# LEDBlink.net
KiCad netlist of a schematic drawn in EAGLE
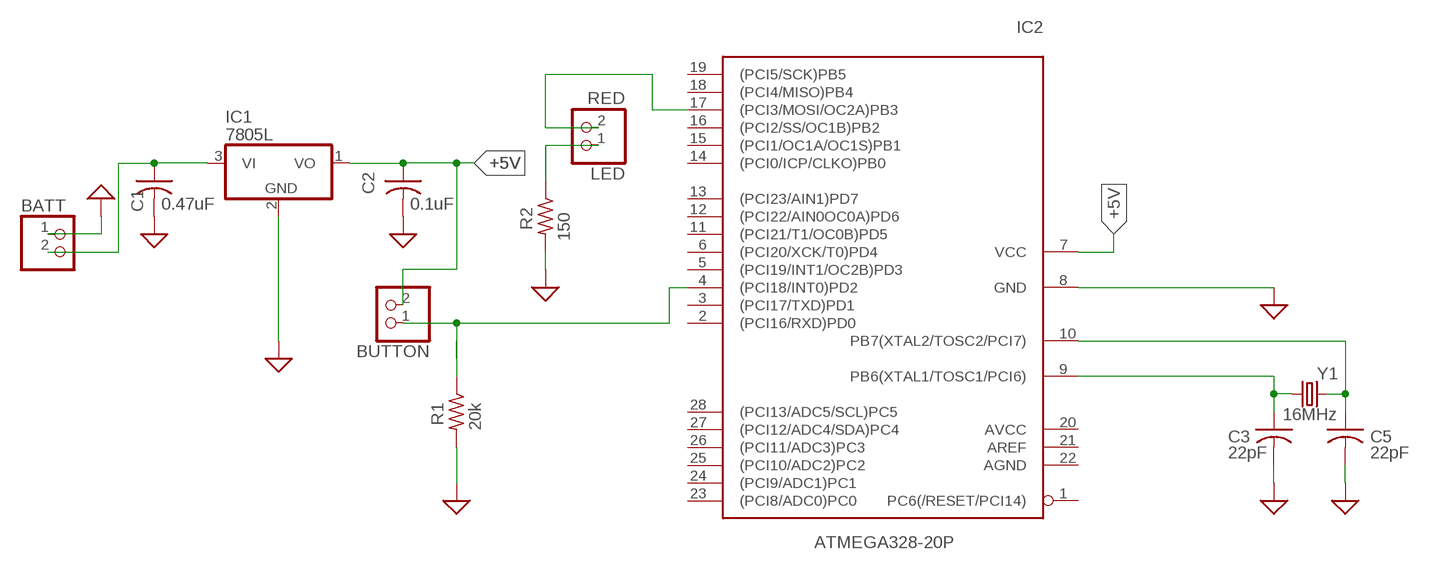
[diagram p0: schematic, sheet 1]

(export (version "E")
  (design (tool "Eeschema 10.0.6"))
  (components
    (comp (ref "BATT")
      (value "PINHD-1X2/90")
      (footprint "eagle-import:1X02_90")
      (libsource (lib "eagle-import") (part "PINHD-1X2/90"))
    )
    (comp (ref "BUTTON")
      (value "PINHD-1X2/90")
      (footprint "eagle-import:1X02_90")
      (libsource (lib "eagle-import") (part "PINHD-1X2/90"))
    )
    (comp (ref "C1")
      (value "0.47uF")
      (footprint "eagle-import:C0805")
      (libsource (lib "eagle-import") (part "C-USC0805"))
    )
    (comp (ref "C2")
      (value "0.1uF")
      (footprint "eagle-import:C0805")
      (libsource (lib "eagle-import") (part "C-USC0805"))
    )
    (comp (ref "C3")
      (value "22pF")
      (footprint "eagle-import:C0805")
      (libsource (lib "eagle-import") (part "C-USC0805"))
    )
    (comp (ref "C5")
      (value "22pF")
      (footprint "eagle-import:C0805")
      (libsource (lib "eagle-import") (part "C-USC0805"))
    )
    (comp (ref "IC1")
      (value "7805L")
      (footprint "eagle-import:TO92")
      (libsource (lib "eagle-import") (part "78L05"))
    )
    (comp (ref "IC2")
      (value "ATMEGA328-20P")
      (footprint "eagle-import:DIL28-3")
      (libsource (lib "eagle-import") (part "ATMEGA328P-20"))
    )
    (comp (ref "LED")
      (value "RED")
      (footprint "eagle-import:1X02_90")
      (libsource (lib "eagle-import") (part "PINHD-1X2/90"))
    )
    (comp (ref "R1")
      (value "20k")
      (footprint "eagle-import:R0805")
      (libsource (lib "eagle-import") (part "R-US_R0805"))
    )
    (comp (ref "R2")
      (value "150")
      (footprint "eagle-import:R0805")
      (libsource (lib "eagle-import") (part "R-US_R0805"))
    )
    (comp (ref "Y1")
      (value "16MHz")
      (footprint "eagle-import:HC49US")
      (libsource (lib "eagle-import") (part "CRYSTAL-16MHZPTH-HC49US"))
    )
  )
  (nets
    (net (code "1") (name "+5V") (class "Default")
      (node (ref "BUTTON") (pin "2") (pinfunction "2_2") (pintype "passive"))
      (node (ref "C2") (pin "1") (pinfunction "1_1") (pintype "passive"))
      (node (ref "IC1") (pin "1") (pinfunction "VO_1") (pintype "passive"))
      (node (ref "IC2") (pin "7") (pinfunction "VCC_7") (pintype "bidirectional"))
    )
    (net (code "2") (name "Net-(IC1-VI)") (class "Default")
      (node (ref "BATT") (pin "2") (pinfunction "2_2") (pintype "passive"))
      (node (ref "C1") (pin "1") (pinfunction "1_1") (pintype "passive"))
      (node (ref "IC1") (pin "3") (pinfunction "VI_3") (pintype "input"))
    )
    (net (code "3") (name "Net-(IC2-(PCI3{slash}MOSI{slash}OC2A)PB3)") (class "Default")
      (node (ref "IC2") (pin "17") (pinfunction "(PCI3/MOSI/OC2A)PB3_17") (pintype "bidirectional"))
      (node (ref "LED") (pin "2") (pinfunction "2_2") (pintype "passive"))
    )
    (net (code "4") (name "Net-(IC2-(PCI18{slash}INT0)PD2)") (class "Default")
      (node (ref "BUTTON") (pin "1") (pinfunction "1_1") (pintype "passive"))
      (node (ref "IC2") (pin "4") (pinfunction "(PCI18/INT0)PD2_4") (pintype "bidirectional"))
      (node (ref "R1") (pin "1") (pinfunction "1_1") (pintype "passive"))
    )
    (net (code "5") (name "Net-(IC2-PB6(XTAL1{slash}TOSC1{slash}PCI6))") (class "Default")
      (node (ref "C3") (pin "1") (pinfunction "1_1") (pintype "passive"))
      (node (ref "IC2") (pin "9") (pinfunction "PB6(XTAL1/TOSC1/PCI6)_9") (pintype "bidirectional"))
      (node (ref "Y1") (pin "1") (pinfunction "1_1") (pintype "passive"))
    )
    (net (code "6") (name "Net-(IC2-PB7(XTAL2{slash}TOSC2{slash}PCI7))") (class "Default")
      (node (ref "C5") (pin "1") (pinfunction "1_1") (pintype "passive"))
      (node (ref "IC2") (pin "10") (pinfunction "PB7(XTAL2/TOSC2/PCI7)_10") (pintype "bidirectional"))
      (node (ref "Y1") (pin "2") (pinfunction "2_2") (pintype "passive"))
    )
    (net (code "7") (name "Net-(LED-Pad1)") (class "Default")
      (node (ref "LED") (pin "1") (pinfunction "1_1") (pintype "passive"))
      (node (ref "R2") (pin "1") (pinfunction "1_1") (pintype "passive"))
    )
    (net (code "8") (name "SUP") (class "Default")
      (node (ref "BATT") (pin "1") (pinfunction "1_1") (pintype "passive"))
      (node (ref "C1") (pin "2") (pinfunction "2_2") (pintype "passive"))
      (node (ref "C2") (pin "2") (pinfunction "2_2") (pintype "passive"))
      (node (ref "C3") (pin "2") (pinfunction "2_2") (pintype "passive"))
      (node (ref "C5") (pin "2") (pinfunction "2_2") (pintype "passive"))
      (node (ref "IC1") (pin "2") (pinfunction "GND_2") (pintype "passive"))
      (node (ref "IC2") (pin "8") (pinfunction "GND_8") (pintype "bidirectional"))
      (node (ref "R1") (pin "2") (pinfunction "2_2") (pintype "passive"))
      (node (ref "R2") (pin "2") (pinfunction "2_2") (pintype "passive"))
    )
    (net (code "9") (name "unconnected-(IC2-(PCI0{slash}ICP{slash}CLKO)PB0-Pad14)") (class "Default")
      (node (ref "IC2") (pin "14") (pinfunction "(PCI0/ICP/CLKO)PB0_14") (pintype "bidirectional"))
    )
    (net (code "10") (name "unconnected-(IC2-(PCI1{slash}OC1A{slash}OC1S)PB1-Pad15)") (class "Default")
      (node (ref "IC2") (pin "15") (pinfunction "(PCI1/OC1A/OC1S)PB1_15") (pintype "bidirectional"))
    )
    (net (code "11") (name "unconnected-(IC2-(PCI2{slash}SS{slash}OC1B)PB2-Pad16)") (class "Default")
      (node (ref "IC2") (pin "16") (pinfunction "(PCI2/SS/OC1B)PB2_16") (pintype "bidirectional"))
    )
    (net (code "12") (name "unconnected-(IC2-(PCI4{slash}MISO)PB4-Pad18)") (class "Default")
      (node (ref "IC2") (pin "18") (pinfunction "(PCI4/MISO)PB4_18") (pintype "bidirectional"))
    )
    (net (code "13") (name "unconnected-(IC2-(PCI5{slash}SCK)PB5-Pad19)") (class "Default")
      (node (ref "IC2") (pin "19") (pinfunction "(PCI5/SCK)PB5_19") (pintype "bidirectional"))
    )
    (net (code "14") (name "unconnected-(IC2-(PCI8{slash}ADC0)PC0-Pad23)") (class "Default")
      (node (ref "IC2") (pin "23") (pinfunction "(PCI8/ADC0)PC0_23") (pintype "bidirectional"))
    )
    (net (code "15") (name "unconnected-(IC2-(PCI9{slash}ADC1)PC1-Pad24)") (class "Default")
      (node (ref "IC2") (pin "24") (pinfunction "(PCI9/ADC1)PC1_24") (pintype "bidirectional"))
    )
    (net (code "16") (name "unconnected-(IC2-(PCI10{slash}ADC2)PC2-Pad25)") (class "Default")
      (node (ref "IC2") (pin "25") (pinfunction "(PCI10/ADC2)PC2_25") (pintype "bidirectional"))
    )
    (net (code "17") (name "unconnected-(IC2-(PCI11{slash}ADC3)PC3-Pad26)") (class "Default")
      (node (ref "IC2") (pin "26") (pinfunction "(PCI11/ADC3)PC3_26") (pintype "bidirectional"))
    )
    (net (code "18") (name "unconnected-(IC2-(PCI12{slash}ADC4{slash}SDA)PC4-Pad27)") (class "Default")
      (node (ref "IC2") (pin "27") (pinfunction "(PCI12/ADC4/SDA)PC4_27") (pintype "bidirectional"))
    )
    (net (code "19") (name "unconnected-(IC2-(PCI13{slash}ADC5{slash}SCL)PC5-Pad28)") (class "Default")
      (node (ref "IC2") (pin "28") (pinfunction "(PCI13/ADC5/SCL)PC5_28") (pintype "bidirectional"))
    )
    (net (code "20") (name "unconnected-(IC2-(PCI16{slash}RXD)PD0-Pad2)") (class "Default")
      (node (ref "IC2") (pin "2") (pinfunction "(PCI16/RXD)PD0_2") (pintype "bidirectional"))
    )
    (net (code "21") (name "unconnected-(IC2-(PCI17{slash}TXD)PD1-Pad3)") (class "Default")
      (node (ref "IC2") (pin "3") (pinfunction "(PCI17/TXD)PD1_3") (pintype "bidirectional"))
    )
    (net (code "22") (name "unconnected-(IC2-(PCI19{slash}INT1{slash}OC2B)PD3-Pad5)") (class "Default")
      (node (ref "IC2") (pin "5") (pinfunction "(PCI19/INT1/OC2B)PD3_5") (pintype "bidirectional"))
    )
    (net (code "23") (name "unconnected-(IC2-(PCI20{slash}XCK{slash}T0)PD4-Pad6)") (class "Default")
      (node (ref "IC2") (pin "6") (pinfunction "(PCI20/XCK/T0)PD4_6") (pintype "bidirectional"))
    )
    (net (code "24") (name "unconnected-(IC2-(PCI21{slash}T1{slash}OC0B)PD5-Pad11)") (class "Default")
      (node (ref "IC2") (pin "11") (pinfunction "(PCI21/T1/OC0B)PD5_11") (pintype "bidirectional"))
    )
    (net (code "25") (name "unconnected-(IC2-(PCI22{slash}AIN0OC0A)PD6-Pad12)") (class "Default")
      (node (ref "IC2") (pin "12") (pinfunction "(PCI22/AIN0OC0A)PD6_12") (pintype "bidirectional"))
    )
    (net (code "26") (name "unconnected-(IC2-(PCI23{slash}AIN1)PD7-Pad13)") (class "Default")
      (node (ref "IC2") (pin "13") (pinfunction "(PCI23/AIN1)PD7_13") (pintype "bidirectional"))
    )
    (net (code "27") (name "unconnected-(IC2-AGND-Pad22)") (class "Default")
      (node (ref "IC2") (pin "22") (pinfunction "AGND_22") (pintype "bidirectional"))
    )
    (net (code "28") (name "unconnected-(IC2-AREF-Pad21)") (class "Default")
      (node (ref "IC2") (pin "21") (pinfunction "AREF_21") (pintype "bidirectional"))
    )
    (net (code "29") (name "unconnected-(IC2-AVCC-Pad20)") (class "Default")
      (node (ref "IC2") (pin "20") (pinfunction "AVCC_20") (pintype "bidirectional"))
    )
    (net (code "30") (name "unconnected-(IC2-PC6({slash}RESET{slash}PCI14)-Pad1)") (class "Default")
      (node (ref "IC2") (pin "1") (pinfunction "PC6(/RESET/PCI14)_1") (pintype "bidirectional"))
    )
  )
)
